# OptoSense.net
KiCad netlist of a schematic drawn in EAGLE
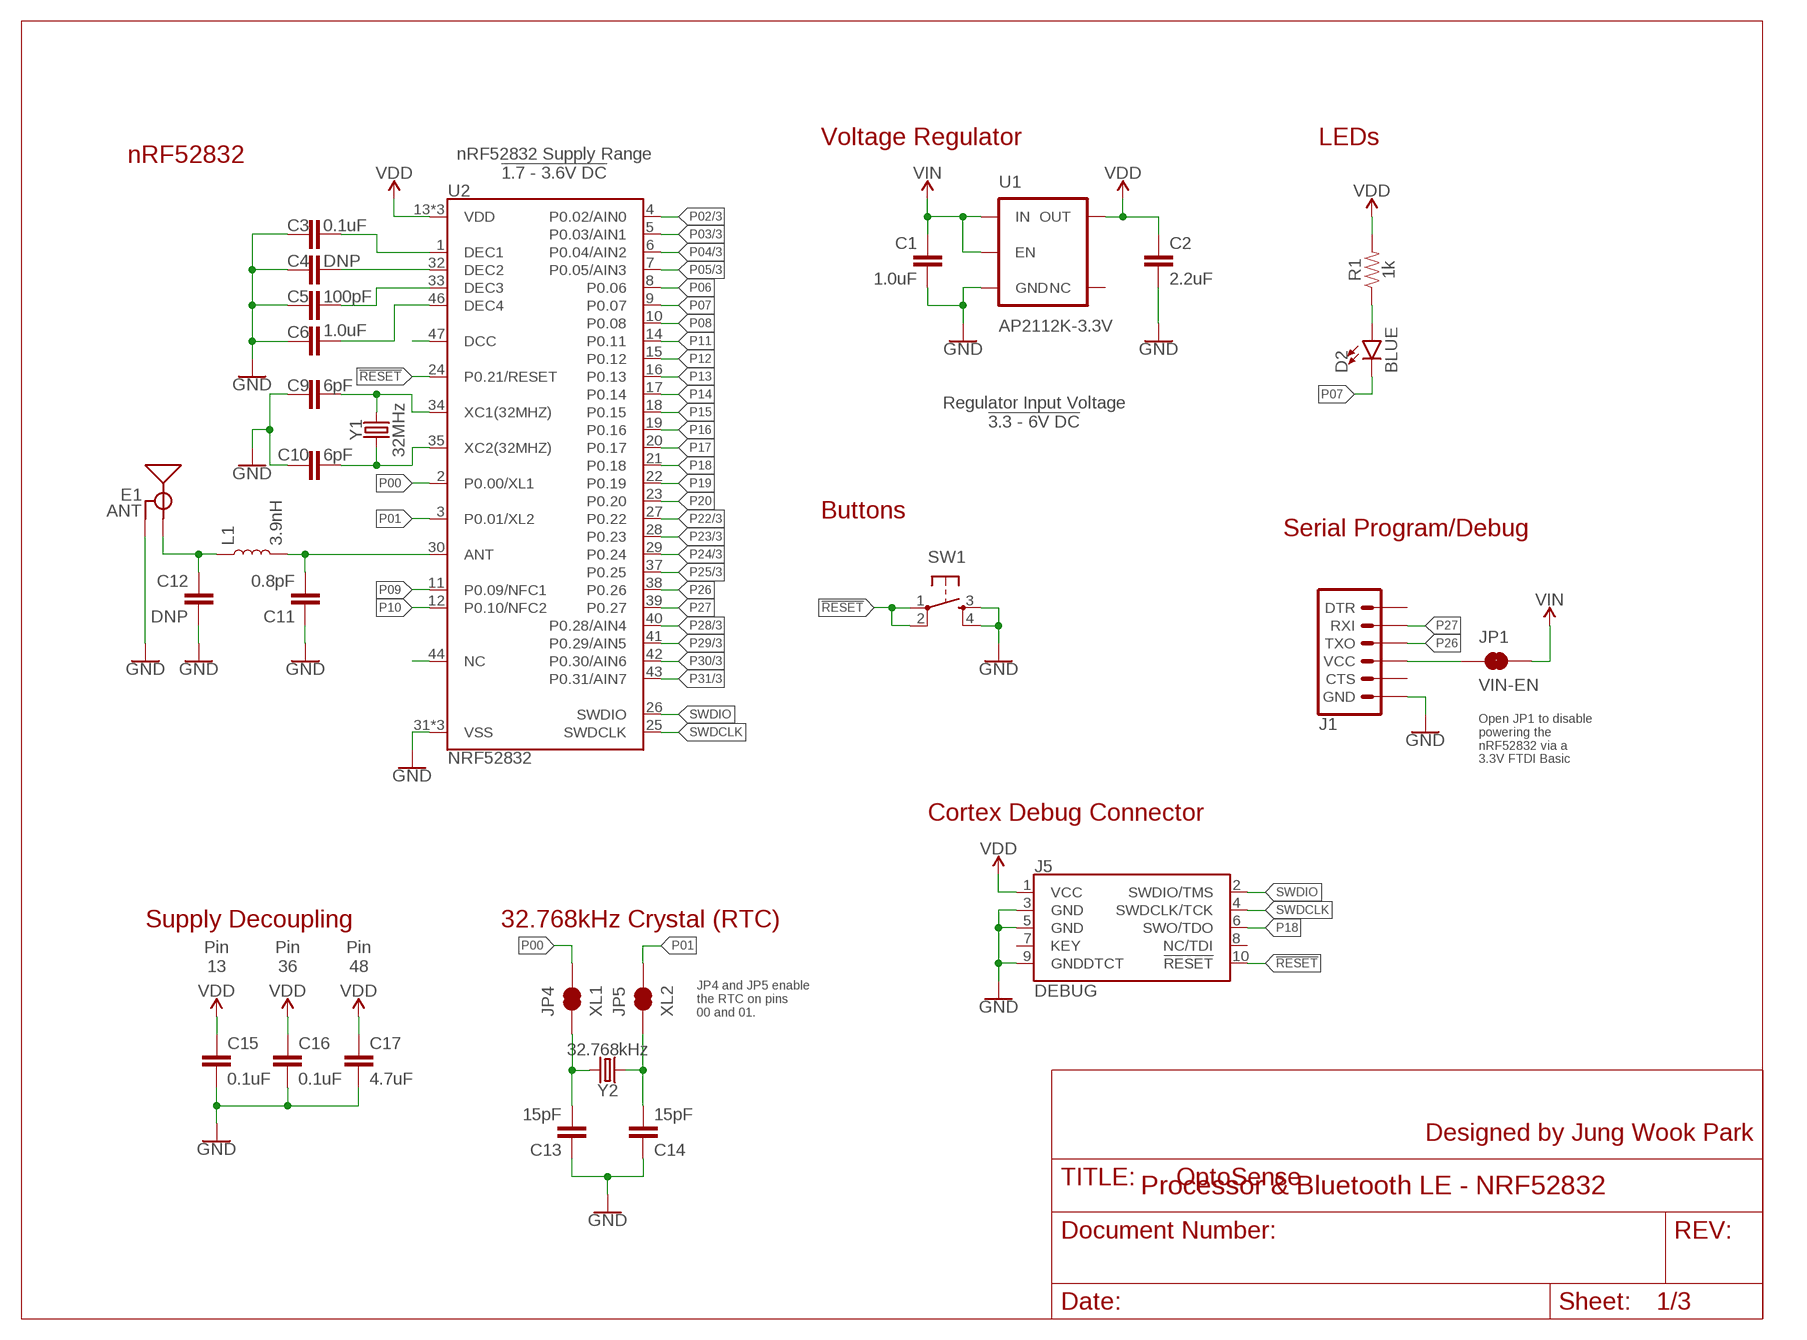
[diagram p0: schematic, sheet 1]
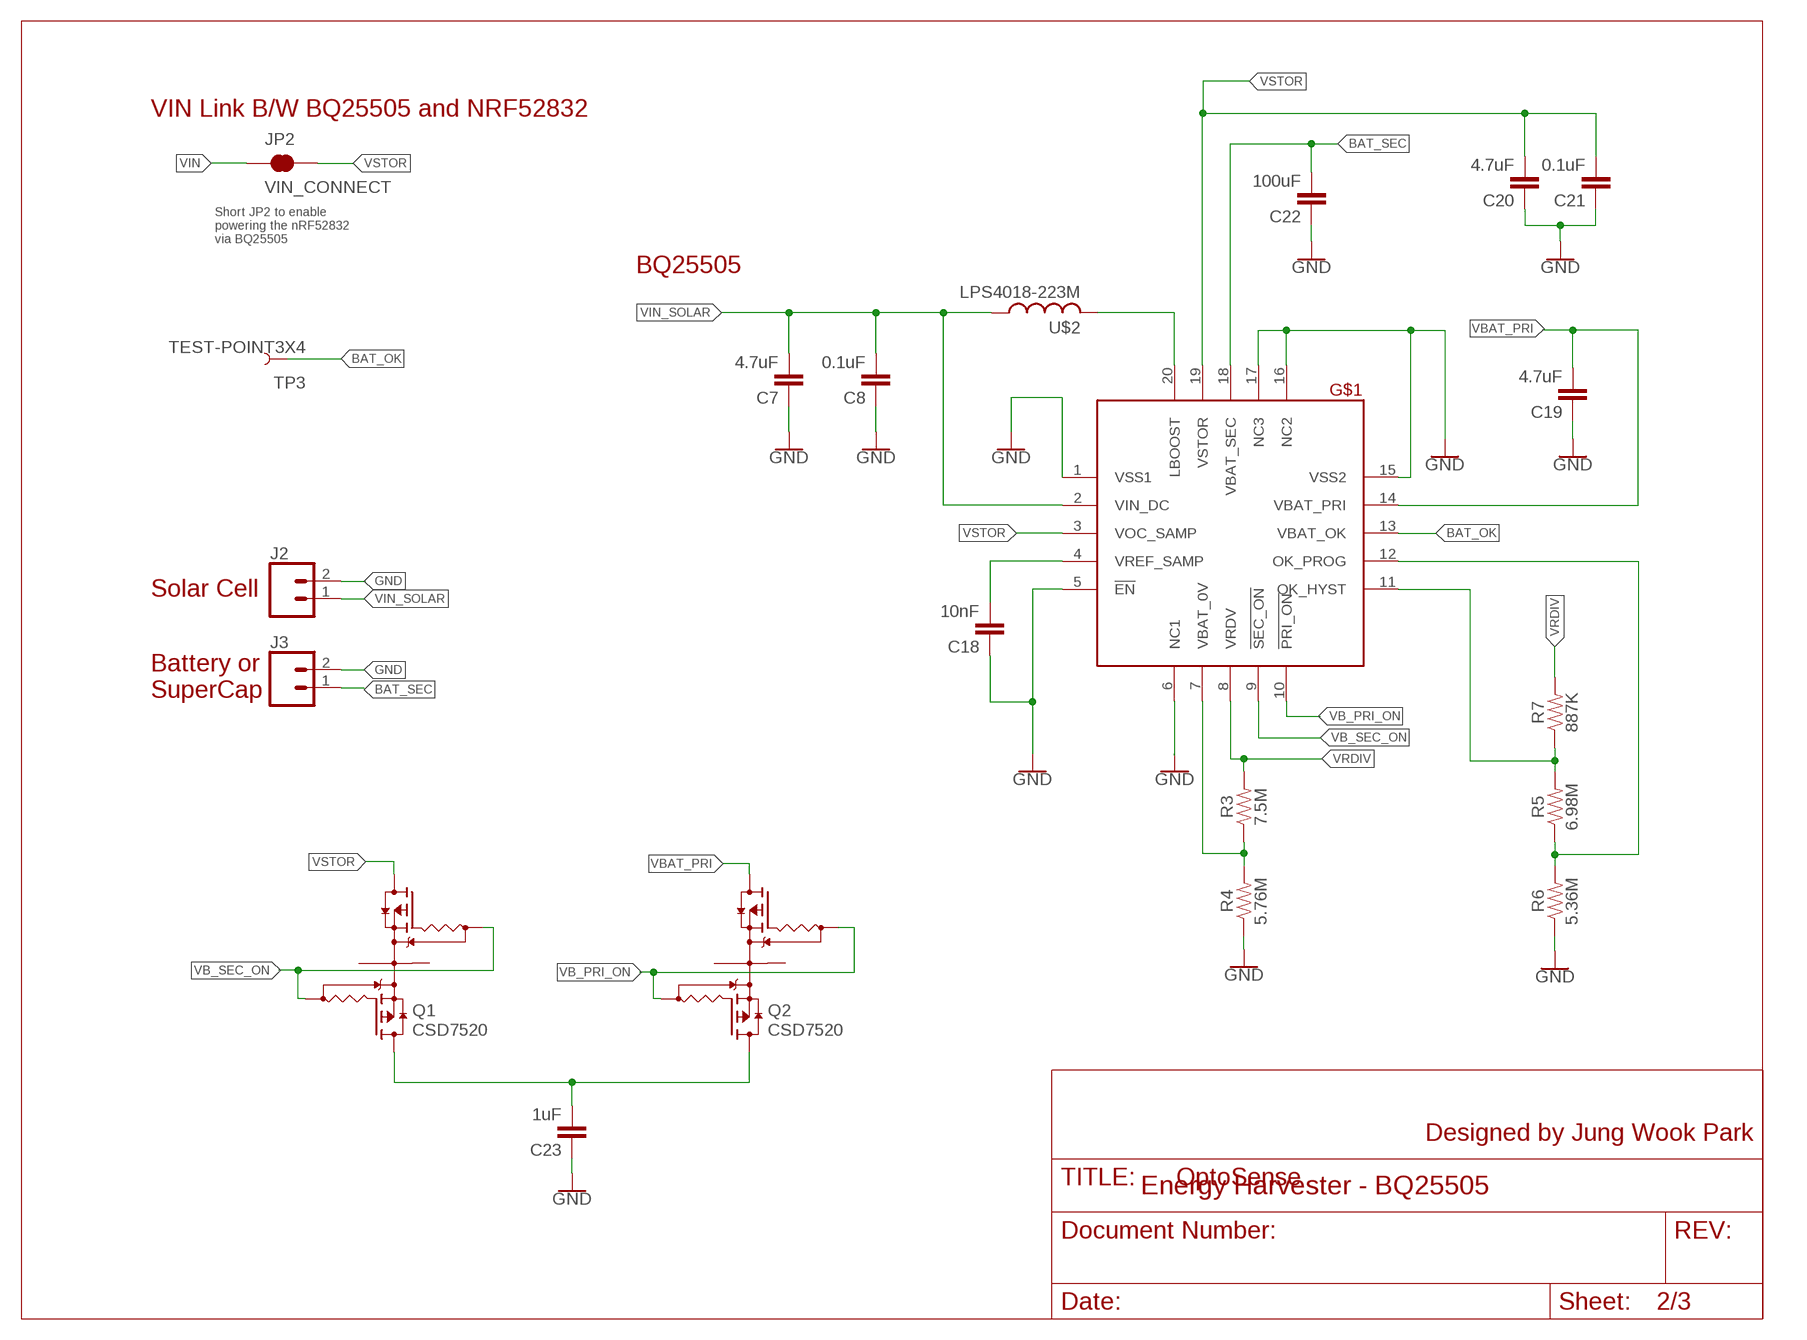
[diagram p1: schematic, sheet 2]
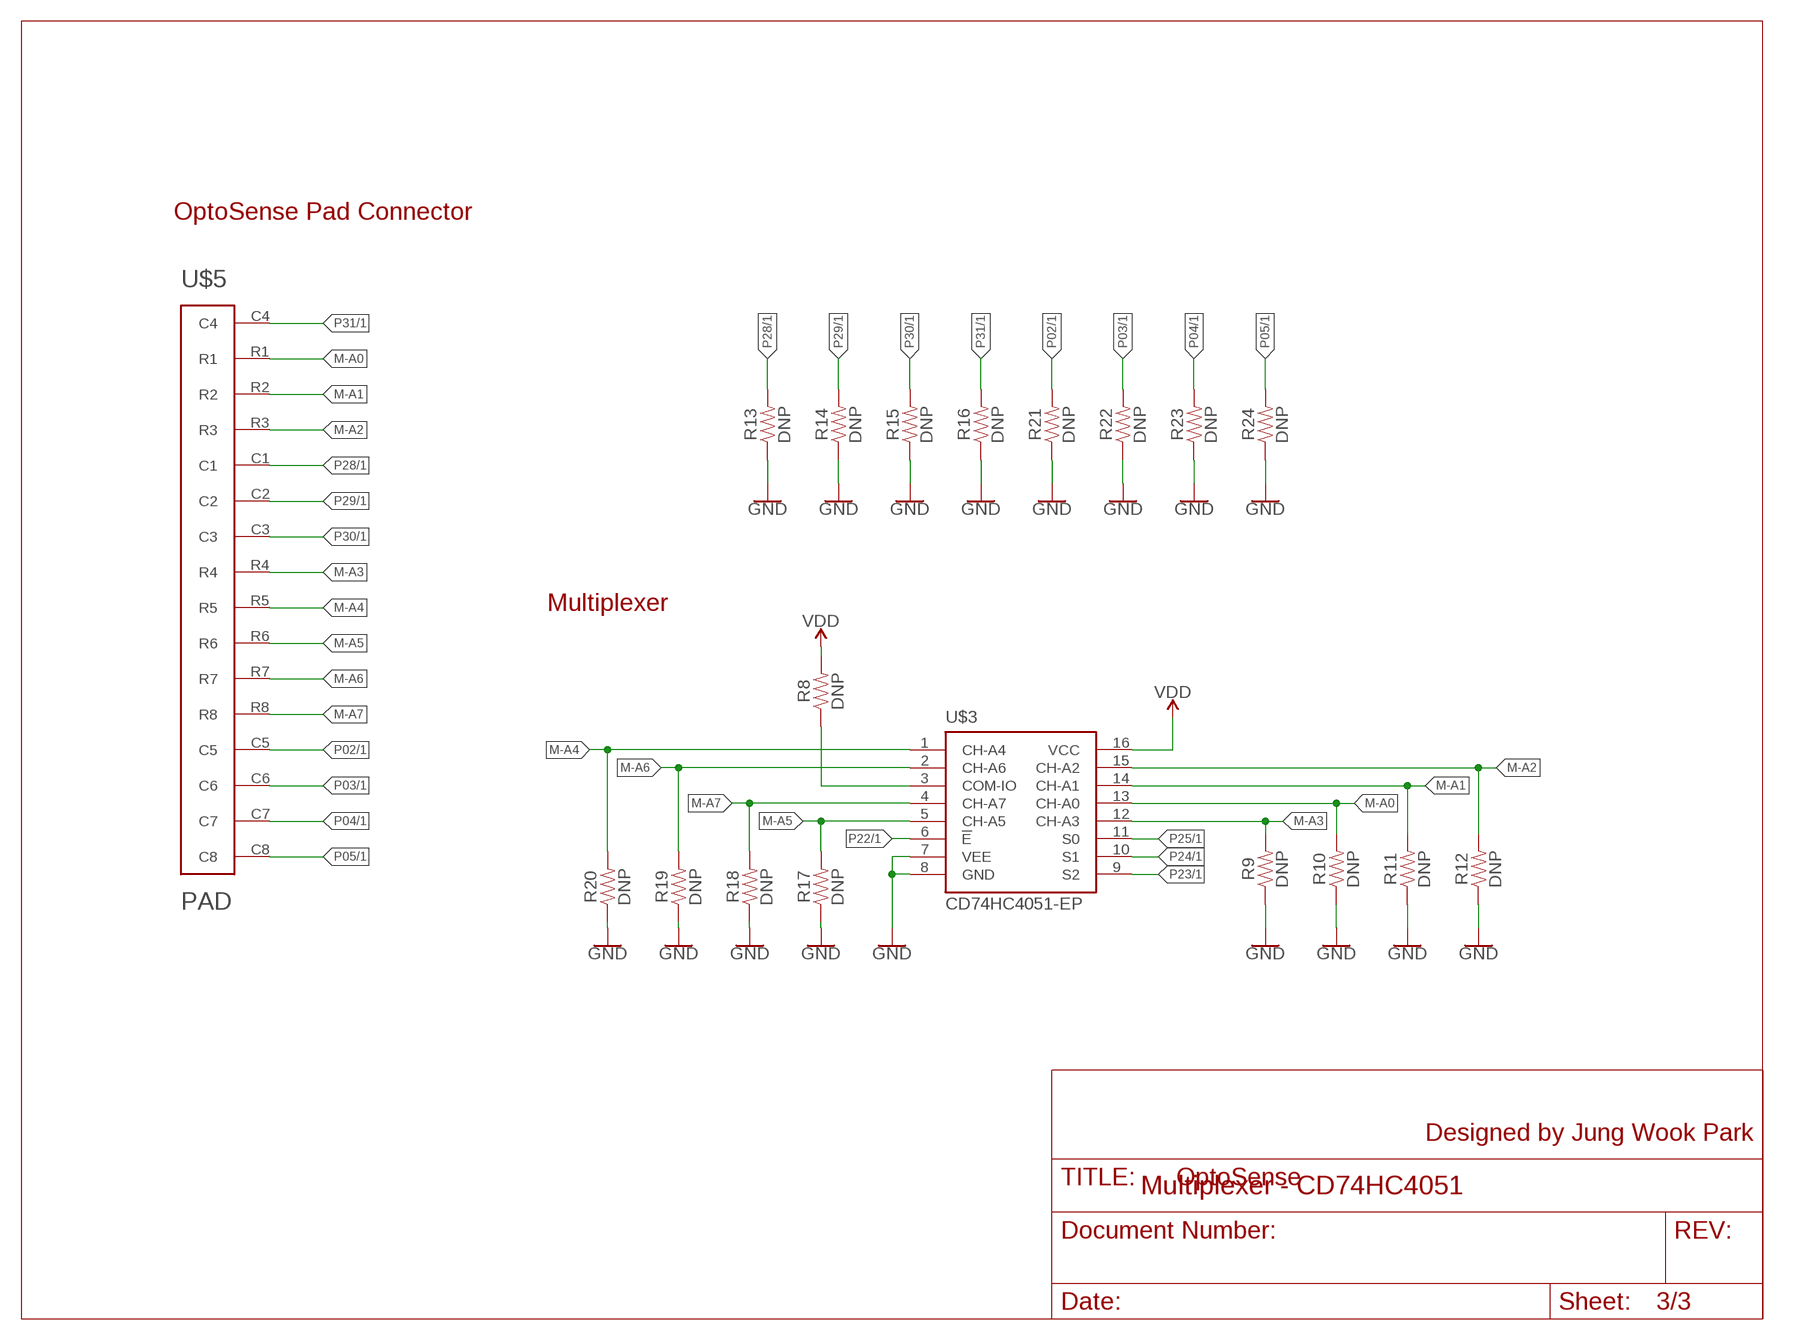
[diagram p2: schematic, sheet 3]

(export (version "E")
  (design (tool "Eeschema 10.0.6"))
  (components
    (comp (ref "C1")
      (value "1.0uF")
      (footprint "eagle-import:0603")
      (libsource (lib "eagle-import") (part "1.0UF-0603-16V-10%"))
    )
    (comp (ref "C2")
      (value "2.2uF")
      (footprint "eagle-import:0603")
      (libsource (lib "eagle-import") (part "2.2UF-0603-10V-20%"))
    )
    (comp (ref "C3")
      (value "0.1uF")
      (footprint "eagle-import:0402")
      (libsource (lib "eagle-import") (part "0.1UF-0402-16V-10%"))
    )
    (comp (ref "C4")
      (value "DNP")
      (footprint "eagle-import:0402")
      (libsource (lib "eagle-import") (part "CAP0402"))
    )
    (comp (ref "C5")
      (value "100pF")
      (footprint "eagle-import:0402")
      (libsource (lib "eagle-import") (part "100PF-0402-50V-5%"))
    )
    (comp (ref "C6")
      (value "1.0uF")
      (footprint "eagle-import:0402")
      (libsource (lib "eagle-import") (part "1.0UF-0402-16V-10%"))
    )
    (comp (ref "C9")
      (value "6pF")
      (footprint "eagle-import:0402")
      (libsource (lib "eagle-import") (part "6PF-0402-50V-0.5%"))
    )
    (comp (ref "C10")
      (value "6pF")
      (footprint "eagle-import:0402")
      (libsource (lib "eagle-import") (part "6PF-0402-50V-0.5%"))
    )
    (comp (ref "C11")
      (value "0.8pF")
      (footprint "eagle-import:0402")
      (libsource (lib "eagle-import") (part "0.8PF-0402-50V-0.1PF"))
    )
    (comp (ref "C12")
      (value "DNP")
      (footprint "eagle-import:0402")
      (libsource (lib "eagle-import") (part "CAP0402"))
    )
    (comp (ref "C13")
      (value "15pF")
      (footprint "eagle-import:0402")
      (libsource (lib "eagle-import") (part "15PF-0402-50V-5%"))
    )
    (comp (ref "C14")
      (value "15pF")
      (footprint "eagle-import:0402")
      (libsource (lib "eagle-import") (part "15PF-0402-50V-5%"))
    )
    (comp (ref "C15")
      (value "0.1uF")
      (footprint "eagle-import:0402")
      (libsource (lib "eagle-import") (part "0.1UF-0402-16V-10%"))
    )
    (comp (ref "C16")
      (value "0.1uF")
      (footprint "eagle-import:0402")
      (libsource (lib "eagle-import") (part "0.1UF-0402-16V-10%"))
    )
    (comp (ref "C17")
      (value "4.7uF")
      (footprint "eagle-import:0603")
      (libsource (lib "eagle-import") (part "4.7UF0603"))
    )
    (comp (ref "D2")
      (value "BLUE")
      (footprint "eagle-import:LED-0603")
      (libsource (lib "eagle-import") (part "LED-BLUE0603"))
    )
    (comp (ref "E1")
      (value "ANT")
      (footprint "eagle-import:TRACE_ANTENNA_2.4GHZ_15.2MM")
      (libsource (lib "eagle-import") (part "ANTENNA-GROUNDEDTRACE-15.2MM"))
    )
    (comp (ref "J1")
      (value "ARDUINO_SERIAL_PROGRAMPTH")
      (footprint "eagle-import:1X06")
      (libsource (lib "eagle-import") (part "ARDUINO_SERIAL_PROGRAMPTH"))
    )
    (comp (ref "J5")
      (value "DEBUG")
      (footprint "eagle-import:2X5-PTH-1.27MM")
      (libsource (lib "eagle-import") (part "CORTEX_DEBUGPTH"))
    )
    (comp (ref "JP1")
      (value "VIN-EN")
      (footprint "eagle-import:SMT-JUMPER_2_NC_TRACE_SILK")
      (libsource (lib "eagle-import") (part "JUMPER-SMT_2_NC_TRACE_SILK"))
    )
    (comp (ref "JP4")
      (value "XL1")
      (footprint "eagle-import:PAD-JUMPER-2-NC_BY_TRACE_YES_SILK")
      (libsource (lib "eagle-import") (part "JUMPER-PAD-2-NC_BY_TRACE"))
    )
    (comp (ref "JP5")
      (value "XL2")
      (footprint "eagle-import:PAD-JUMPER-2-NC_BY_TRACE_YES_SILK")
      (libsource (lib "eagle-import") (part "JUMPER-PAD-2-NC_BY_TRACE"))
    )
    (comp (ref "L1")
      (value "3.9nH")
      (footprint "eagle-import:0402")
      (libsource (lib "eagle-import") (part "INDUCTOR-0402-3.9NH"))
    )
    (comp (ref "R1")
      (value "1k")
      (footprint "eagle-import:0603")
      (libsource (lib "eagle-import") (part "1KOHM-0603-1/10W-1%"))
    )
    (comp (ref "SW1")
      (value "SWITCH_SPST_4_PINRECT")
      (footprint "eagle-import:TACTILE_SWITCH_SMD_4.6X2.8MM")
      (libsource (lib "eagle-import") (part "SWITCH_SPST_4_PINRECT"))
    )
    (comp (ref "U1")
      (value "AP2112K-3.3V")
      (footprint "eagle-import:SOT23-5")
      (libsource (lib "eagle-import") (part "V_REG_AP2112K-3.3V"))
    )
    (comp (ref "U2")
      (value "NRF52832")
      (footprint "eagle-import:QFN48-6X6MM")
      (libsource (lib "eagle-import") (part "NRF52832"))
    )
    (comp (ref "Y1")
      (value "32MHz")
      (footprint "eagle-import:CRYSTAL-SMD-2.0X1.6MM")
      (libsource (lib "eagle-import") (part "CRYSTAL-32MHZ-SMD-2.0X1.6MM"))
    )
    (comp (ref "Y2")
      (value "32.768kHz")
      (footprint "eagle-import:CRYSTAL-SMD-3.2X1.5MM")
      (libsource (lib "eagle-import") (part "CRYSTAL-32.768KHZSMD-3.2X1.5"))
    )
    (comp (ref "C7")
      (value "4.7uF")
      (footprint "eagle-import:0402")
      (libsource (lib "eagle-import") (part "0.8PF-0402-50V-0.1PF"))
    )
    (comp (ref "C8")
      (value "0.1uF")
      (footprint "eagle-import:0402")
      (libsource (lib "eagle-import") (part "0.8PF-0402-50V-0.1PF"))
    )
    (comp (ref "C18")
      (value "10nF")
      (footprint "eagle-import:0402")
      (libsource (lib "eagle-import") (part "0.8PF-0402-50V-0.1PF"))
    )
    (comp (ref "C19")
      (value "4.7uF")
      (footprint "eagle-import:0402")
      (libsource (lib "eagle-import") (part "0.8PF-0402-50V-0.1PF"))
    )
    (comp (ref "C20")
      (value "4.7uF")
      (footprint "eagle-import:0402")
      (libsource (lib "eagle-import") (part "0.8PF-0402-50V-0.1PF"))
    )
    (comp (ref "C21")
      (value "0.1uF")
      (footprint "eagle-import:0402")
      (libsource (lib "eagle-import") (part "0.8PF-0402-50V-0.1PF"))
    )
    (comp (ref "C22")
      (value "100uF")
      (footprint "eagle-import:0402")
      (libsource (lib "eagle-import") (part "0.8PF-0402-50V-0.1PF"))
    )
    (comp (ref "C23")
      (value "1uF")
      (footprint "eagle-import:0402")
      (libsource (lib "eagle-import") (part "0.8PF-0402-50V-0.1PF"))
    )
    (comp (ref "J2")
      (value "CONN_02")
      (footprint "eagle-import:1X02")
      (libsource (lib "eagle-import") (part "CONN_02"))
    )
    (comp (ref "J3")
      (value "CONN_02")
      (footprint "eagle-import:1X02")
      (libsource (lib "eagle-import") (part "CONN_02"))
    )
    (comp (ref "JP2")
      (value "VIN_CONNECT")
      (footprint "eagle-import:SMT-JUMPER_2_NC_TRACE_SILK")
      (libsource (lib "eagle-import") (part "JUMPER-SMT_2_NC_TRACE_SILK"))
    )
    (comp (ref "Q1")
      (value "CSD7520")
      (footprint "eagle-import:CSD75205W1015")
      (libsource (lib "eagle-import") (part "CSD75205W1015-BGA"))
    )
    (comp (ref "Q2")
      (value "CSD7520")
      (footprint "eagle-import:CSD75205W1015")
      (libsource (lib "eagle-import") (part "CSD75205W1015-BGA"))
    )
    (comp (ref "R3")
      (value "7.5M")
      (footprint "eagle-import:0603")
      (libsource (lib "eagle-import") (part "1KOHM-0603-1/10W-1%"))
    )
    (comp (ref "R4")
      (value "5.76M")
      (footprint "eagle-import:0603")
      (libsource (lib "eagle-import") (part "1KOHM-0603-1/10W-1%"))
    )
    (comp (ref "R5")
      (value "6.98M")
      (footprint "eagle-import:0603")
      (libsource (lib "eagle-import") (part "1KOHM-0603-1/10W-1%"))
    )
    (comp (ref "R6")
      (value "5.36M")
      (footprint "eagle-import:0603")
      (libsource (lib "eagle-import") (part "1KOHM-0603-1/10W-1%"))
    )
    (comp (ref "R7")
      (value "887K")
      (footprint "eagle-import:0603")
      (libsource (lib "eagle-import") (part "1KOHM-0603-1/10W-1%"))
    )
    (comp (ref "TP3")
      (value "TEST-POINT3X4")
      (footprint "eagle-import:PAD.03X.04")
      (libsource (lib "eagle-import") (part "TEST-POINT3X4"))
    )
    (comp (ref "U$1")
      (value "BQ25505")
      (footprint "eagle-import:QFN20")
      (libsource (lib "eagle-import") (part "BQ25505"))
    )
    (comp (ref "U$2")
      (value "LPS4018-223M")
      (footprint "eagle-import:LPS4018")
      (libsource (lib "eagle-import") (part "LPS4018"))
    )
    (comp (ref "R8")
      (value "DNP")
      (footprint "eagle-import:0603")
      (libsource (lib "eagle-import") (part "1KOHM-0603-1/10W-1%"))
    )
    (comp (ref "R9")
      (value "DNP")
      (footprint "eagle-import:0603")
      (libsource (lib "eagle-import") (part "1KOHM-0603-1/10W-1%"))
    )
    (comp (ref "R10")
      (value "DNP")
      (footprint "eagle-import:0603")
      (libsource (lib "eagle-import") (part "1KOHM-0603-1/10W-1%"))
    )
    (comp (ref "R11")
      (value "DNP")
      (footprint "eagle-import:0603")
      (libsource (lib "eagle-import") (part "1KOHM-0603-1/10W-1%"))
    )
    (comp (ref "R12")
      (value "DNP")
      (footprint "eagle-import:0603")
      (libsource (lib "eagle-import") (part "1KOHM-0603-1/10W-1%"))
    )
    (comp (ref "R13")
      (value "DNP")
      (footprint "eagle-import:0603")
      (libsource (lib "eagle-import") (part "1KOHM-0603-1/10W-1%"))
    )
    (comp (ref "R14")
      (value "DNP")
      (footprint "eagle-import:0603")
      (libsource (lib "eagle-import") (part "1KOHM-0603-1/10W-1%"))
    )
    (comp (ref "R15")
      (value "DNP")
      (footprint "eagle-import:0603")
      (libsource (lib "eagle-import") (part "1KOHM-0603-1/10W-1%"))
    )
    (comp (ref "R16")
      (value "DNP")
      (footprint "eagle-import:0603")
      (libsource (lib "eagle-import") (part "1KOHM-0603-1/10W-1%"))
    )
    (comp (ref "R17")
      (value "DNP")
      (footprint "eagle-import:0603")
      (libsource (lib "eagle-import") (part "1KOHM-0603-1/10W-1%"))
    )
    (comp (ref "R18")
      (value "DNP")
      (footprint "eagle-import:0603")
      (libsource (lib "eagle-import") (part "1KOHM-0603-1/10W-1%"))
    )
    (comp (ref "R19")
      (value "DNP")
      (footprint "eagle-import:0603")
      (libsource (lib "eagle-import") (part "1KOHM-0603-1/10W-1%"))
    )
    (comp (ref "R20")
      (value "DNP")
      (footprint "eagle-import:0603")
      (libsource (lib "eagle-import") (part "1KOHM-0603-1/10W-1%"))
    )
    (comp (ref "R21")
      (value "DNP")
      (footprint "eagle-import:0603")
      (libsource (lib "eagle-import") (part "1KOHM-0603-1/10W-1%"))
    )
    (comp (ref "R22")
      (value "DNP")
      (footprint "eagle-import:0603")
      (libsource (lib "eagle-import") (part "1KOHM-0603-1/10W-1%"))
    )
    (comp (ref "R23")
      (value "DNP")
      (footprint "eagle-import:0603")
      (libsource (lib "eagle-import") (part "1KOHM-0603-1/10W-1%"))
    )
    (comp (ref "R24")
      (value "DNP")
      (footprint "eagle-import:0603")
      (libsource (lib "eagle-import") (part "1KOHM-0603-1/10W-1%"))
    )
    (comp (ref "U$3")
      (value "CD74HC4051-EP")
      (footprint "eagle-import:SO16")
      (libsource (lib "eagle-import") (part "CD74HC4051-EP"))
    )
    (comp (ref "U$5")
      (value "PAD")
      (footprint "eagle-import:PADS-16")
      (libsource (lib "eagle-import") (part "OPTOSENSE_PAD_CONNECTOR16"))
    )
  )
  (nets
    (net (code "1") (name "BAT_OK") (class "Default")
      (node (ref "TP3") (pin "P$1") (pinfunction "1_P$1") (pintype "bidirectional"))
      (node (ref "U$1") (pin "13") (pinfunction "VBAT_OK_13") (pintype "bidirectional"))
    )
    (net (code "2") (name "BAT_SEC") (class "Default")
      (node (ref "C22") (pin "2") (pinfunction "2_2") (pintype "passive"))
      (node (ref "J3") (pin "1") (pinfunction "1_1") (pintype "passive"))
      (node (ref "U$1") (pin "18") (pinfunction "VBAT_SEC_18") (pintype "bidirectional"))
    )
    (net (code "3") (name "GND") (class "Default")
      (node (ref "C1") (pin "2") (pinfunction "2_2") (pintype "passive"))
      (node (ref "C10") (pin "2") (pinfunction "2_2") (pintype "passive"))
      (node (ref "C11") (pin "1") (pinfunction "1_1") (pintype "passive"))
      (node (ref "C12") (pin "2") (pinfunction "2_2") (pintype "passive"))
      (node (ref "C13") (pin "1") (pinfunction "1_1") (pintype "passive"))
      (node (ref "C14") (pin "1") (pinfunction "1_1") (pintype "passive"))
      (node (ref "C15") (pin "2") (pinfunction "2_2") (pintype "passive"))
      (node (ref "C16") (pin "2") (pinfunction "2_2") (pintype "passive"))
      (node (ref "C17") (pin "2") (pinfunction "2_2") (pintype "passive"))
      (node (ref "C18") (pin "1") (pinfunction "1_1") (pintype "passive"))
      (node (ref "C19") (pin "1") (pinfunction "1_1") (pintype "passive"))
      (node (ref "C2") (pin "2") (pinfunction "2_2") (pintype "passive"))
      (node (ref "C20") (pin "1") (pinfunction "1_1") (pintype "passive"))
      (node (ref "C21") (pin "1") (pinfunction "1_1") (pintype "passive"))
      (node (ref "C22") (pin "1") (pinfunction "1_1") (pintype "passive"))
      (node (ref "C23") (pin "1") (pinfunction "1_1") (pintype "passive"))
      (node (ref "C3") (pin "1") (pinfunction "1_1") (pintype "passive"))
      (node (ref "C4") (pin "1") (pinfunction "1_1") (pintype "passive"))
      (node (ref "C5") (pin "1") (pinfunction "1_1") (pintype "passive"))
      (node (ref "C6") (pin "1") (pinfunction "1_1") (pintype "passive"))
      (node (ref "C7") (pin "1") (pinfunction "1_1") (pintype "passive"))
      (node (ref "C8") (pin "1") (pinfunction "1_1") (pintype "passive"))
      (node (ref "C9") (pin "1") (pinfunction "1_1") (pintype "passive"))
      (node (ref "E1") (pin "GND") (pinfunction "GND_GND") (pintype "bidirectional"))
      (node (ref "J1") (pin "6") (pinfunction "GND_6") (pintype "passive"))
      (node (ref "J2") (pin "2") (pinfunction "2_2") (pintype "passive"))
      (node (ref "J3") (pin "2") (pinfunction "2_2") (pintype "passive"))
      (node (ref "J5") (pin "3") (pinfunction "GND_3") (pintype "bidirectional"))
      (node (ref "J5") (pin "5") (pinfunction "GND_5") (pintype "bidirectional"))
      (node (ref "J5") (pin "9") (pinfunction "GNDDTCT_9") (pintype "bidirectional"))
      (node (ref "R10") (pin "1") (pinfunction "1_1") (pintype "passive"))
      (node (ref "R11") (pin "1") (pinfunction "1_1") (pintype "passive"))
      (node (ref "R12") (pin "1") (pinfunction "1_1") (pintype "passive"))
      (node (ref "R13") (pin "1") (pinfunction "1_1") (pintype "passive"))
      (node (ref "R14") (pin "1") (pinfunction "1_1") (pintype "passive"))
      (node (ref "R15") (pin "1") (pinfunction "1_1") (pintype "passive"))
      (node (ref "R16") (pin "1") (pinfunction "1_1") (pintype "passive"))
      (node (ref "R17") (pin "1") (pinfunction "1_1") (pintype "passive"))
      (node (ref "R18") (pin "1") (pinfunction "1_1") (pintype "passive"))
      (node (ref "R19") (pin "1") (pinfunction "1_1") (pintype "passive"))
      (node (ref "R20") (pin "1") (pinfunction "1_1") (pintype "passive"))
      (node (ref "R21") (pin "1") (pinfunction "1_1") (pintype "passive"))
      (node (ref "R22") (pin "1") (pinfunction "1_1") (pintype "passive"))
      (node (ref "R23") (pin "1") (pinfunction "1_1") (pintype "passive"))
      (node (ref "R24") (pin "1") (pinfunction "1_1") (pintype "passive"))
      (node (ref "R4") (pin "1") (pinfunction "1_1") (pintype "passive"))
      (node (ref "R6") (pin "1") (pinfunction "1_1") (pintype "passive"))
      (node (ref "R9") (pin "1") (pinfunction "1_1") (pintype "passive"))
      (node (ref "SW1") (pin "3") (pinfunction "3_3") (pintype "passive"))
      (node (ref "SW1") (pin "4") (pinfunction "4_4") (pintype "passive"))
      (node (ref "U$1") (pin "1") (pinfunction "VSS1_1") (pintype "bidirectional"))
      (node (ref "U$1") (pin "15") (pinfunction "VSS2_15") (pintype "bidirectional"))
      (node (ref "U$1") (pin "16") (pinfunction "NC2_16") (pintype "bidirectional"))
      (node (ref "U$1") (pin "17") (pinfunction "NC3_17") (pintype "bidirectional"))
      (node (ref "U$1") (pin "5") (pinfunction "~{EN}_5") (pintype "bidirectional"))
      (node (ref "U$1") (pin "6") (pinfunction "NC1_6") (pintype "bidirectional"))
      (node (ref "U$3") (pin "7") (pinfunction "VEE_7") (pintype "bidirectional"))
      (node (ref "U$3") (pin "8") (pinfunction "GND_8") (pintype "bidirectional"))
      (node (ref "U1") (pin "2") (pinfunction "GND_2") (pintype "input"))
      (node (ref "U2") (pin "31") (pinfunction "VSS_31") (pintype "bidirectional"))
      (node (ref "U2") (pin "45") (pinfunction "VSS_45") (pintype "bidirectional"))
      (node (ref "U2") (pin "EP") (pinfunction "VSS_EP") (pintype "bidirectional"))
    )
    (net (code "4") (name "M-A0") (class "Default")
      (node (ref "R10") (pin "2") (pinfunction "2_2") (pintype "passive"))
      (node (ref "U$3") (pin "13") (pinfunction "CH-A0_13") (pintype "bidirectional"))
      (node (ref "U$5") (pin "R1") (pinfunction "R1_R1") (pintype "bidirectional"))
    )
    (net (code "5") (name "M-A1") (class "Default")
      (node (ref "R11") (pin "2") (pinfunction "2_2") (pintype "passive"))
      (node (ref "U$3") (pin "14") (pinfunction "CH-A1_14") (pintype "bidirectional"))
      (node (ref "U$5") (pin "R2") (pinfunction "R2_R2") (pintype "bidirectional"))
    )
    (net (code "6") (name "M-A2") (class "Default")
      (node (ref "R12") (pin "2") (pinfunction "2_2") (pintype "passive"))
      (node (ref "U$3") (pin "15") (pinfunction "CH-A2_15") (pintype "bidirectional"))
      (node (ref "U$5") (pin "R3") (pinfunction "R3_R3") (pintype "bidirectional"))
    )
    (net (code "7") (name "M-A3") (class "Default")
      (node (ref "R9") (pin "2") (pinfunction "2_2") (pintype "passive"))
      (node (ref "U$3") (pin "12") (pinfunction "CH-A3_12") (pintype "bidirectional"))
      (node (ref "U$5") (pin "R4") (pinfunction "R4_R4") (pintype "bidirectional"))
    )
    (net (code "8") (name "M-A4") (class "Default")
      (node (ref "R20") (pin "2") (pinfunction "2_2") (pintype "passive"))
      (node (ref "U$3") (pin "1") (pinfunction "CH-A4_1") (pintype "bidirectional"))
      (node (ref "U$5") (pin "R5") (pinfunction "R5_R5") (pintype "bidirectional"))
    )
    (net (code "9") (name "M-A5") (class "Default")
      (node (ref "R17") (pin "2") (pinfunction "2_2") (pintype "passive"))
      (node (ref "U$3") (pin "5") (pinfunction "CH-A5_5") (pintype "bidirectional"))
      (node (ref "U$5") (pin "R6") (pinfunction "R6_R6") (pintype "bidirectional"))
    )
    (net (code "10") (name "M-A6") (class "Default")
      (node (ref "R19") (pin "2") (pinfunction "2_2") (pintype "passive"))
      (node (ref "U$3") (pin "2") (pinfunction "CH-A6_2") (pintype "bidirectional"))
      (node (ref "U$5") (pin "R7") (pinfunction "R7_R7") (pintype "bidirectional"))
    )
    (net (code "11") (name "M-A7") (class "Default")
      (node (ref "R18") (pin "2") (pinfunction "2_2") (pintype "passive"))
      (node (ref "U$3") (pin "4") (pinfunction "CH-A7_4") (pintype "bidirectional"))
      (node (ref "U$5") (pin "R8") (pinfunction "R8_R8") (pintype "bidirectional"))
    )
    (net (code "12") (name "Net-(C23-Pad2)") (class "Default")
      (node (ref "C23") (pin "2") (pinfunction "2_2") (pintype "passive"))
      (node (ref "Q1") (pin "D1") (pinfunction "D1_D1") (pintype "passive"))
      (node (ref "Q2") (pin "D1") (pinfunction "D1_D1") (pintype "passive"))
    )
    (net (code "13") (name "Net-(D2-PadA)") (class "Default")
      (node (ref "D2") (pin "A") (pinfunction "A_A") (pintype "passive"))
      (node (ref "R1") (pin "1") (pinfunction "1_1") (pintype "passive"))
    )
    (net (code "14") (name "Net-(E1-SIGNAL)") (class "Default")
      (node (ref "C12") (pin "1") (pinfunction "1_1") (pintype "passive"))
      (node (ref "E1") (pin "ANT") (pinfunction "SIGNAL_ANT") (pintype "bidirectional"))
      (node (ref "L1") (pin "1") (pinfunction "1_1") (pintype "passive"))
    )
    (net (code "15") (name "Net-(J1-VCC)") (class "Default")
      (node (ref "J1") (pin "4") (pinfunction "VCC_4") (pintype "passive"))
      (node (ref "JP1") (pin "1") (pinfunction "1_1") (pintype "passive"))
    )
    (net (code "16") (name "Net-(U$1-LBOOST)") (class "Default")
      (node (ref "U$1") (pin "20") (pinfunction "LBOOST_20") (pintype "bidirectional"))
      (node (ref "U$2") (pin "P$2") (pinfunction "2_P$2") (pintype "passive"))
    )
    (net (code "17") (name "Net-(U$1-OK_HYST)") (class "Default")
      (node (ref "R5") (pin "2") (pinfunction "2_2") (pintype "passive"))
      (node (ref "R7") (pin "1") (pinfunction "1_1") (pintype "passive"))
      (node (ref "U$1") (pin "11") (pinfunction "OK_HYST_11") (pintype "bidirectional"))
    )
    (net (code "18") (name "Net-(U$1-OK_PROG)") (class "Default")
      (node (ref "R5") (pin "1") (pinfunction "1_1") (pintype "passive"))
      (node (ref "R6") (pin "2") (pinfunction "2_2") (pintype "passive"))
      (node (ref "U$1") (pin "12") (pinfunction "OK_PROG_12") (pintype "bidirectional"))
    )
    (net (code "19") (name "Net-(U$1-VBAT_0V)") (class "Default")
      (node (ref "R3") (pin "1") (pinfunction "1_1") (pintype "passive"))
      (node (ref "R4") (pin "2") (pinfunction "2_2") (pintype "passive"))
      (node (ref "U$1") (pin "7") (pinfunction "VBAT_0V_7") (pintype "bidirectional"))
    )
    (net (code "20") (name "Net-(U$1-VREF_SAMP)") (class "Default")
      (node (ref "C18") (pin "2") (pinfunction "2_2") (pintype "passive"))
      (node (ref "U$1") (pin "4") (pinfunction "VREF_SAMP_4") (pintype "bidirectional"))
    )
    (net (code "21") (name "Net-(U$3-COM-IO)") (class "Default")
      (node (ref "R8") (pin "1") (pinfunction "1_1") (pintype "passive"))
      (node (ref "U$3") (pin "3") (pinfunction "COM-IO_3") (pintype "bidirectional"))
    )
    (net (code "22") (name "Net-(U2-ANT)") (class "Default")
      (node (ref "C11") (pin "2") (pinfunction "2_2") (pintype "passive"))
      (node (ref "L1") (pin "2") (pinfunction "2_2") (pintype "passive"))
      (node (ref "U2") (pin "30") (pinfunction "ANT_30") (pintype "bidirectional"))
    )
    (net (code "23") (name "Net-(U2-DEC1)") (class "Default")
      (node (ref "C3") (pin "2") (pinfunction "2_2") (pintype "passive"))
      (node (ref "U2") (pin "1") (pinfunction "DEC1_1") (pintype "bidirectional"))
    )
    (net (code "24") (name "Net-(U2-DEC2)") (class "Default")
      (node (ref "C4") (pin "2") (pinfunction "2_2") (pintype "passive"))
      (node (ref "U2") (pin "32") (pinfunction "DEC2_32") (pintype "bidirectional"))
    )
    (net (code "25") (name "Net-(U2-DEC3)") (class "Default")
      (node (ref "C5") (pin "2") (pinfunction "2_2") (pintype "passive"))
      (node (ref "U2") (pin "33") (pinfunction "DEC3_33") (pintype "bidirectional"))
    )
    (net (code "26") (name "Net-(U2-DEC4)") (class "Default")
      (node (ref "C6") (pin "2") (pinfunction "2_2") (pintype "passive"))
      (node (ref "U2") (pin "46") (pinfunction "DEC4_46") (pintype "bidirectional"))
    )
    (net (code "27") (name "Net-(U2-XC1(32MHZ))") (class "Default")
      (node (ref "C9") (pin "2") (pinfunction "2_2") (pintype "passive"))
      (node (ref "U2") (pin "34") (pinfunction "XC1(32MHZ)_34") (pintype "bidirectional"))
      (node (ref "Y1") (pin "3") (pinfunction "2_3") (pintype "passive"))
    )
    (net (code "28") (name "Net-(U2-XC2(32MHZ))") (class "Default")
      (node (ref "C10") (pin "1") (pinfunction "1_1") (pintype "passive"))
      (node (ref "U2") (pin "35") (pinfunction "XC2(32MHZ)_35") (pintype "bidirectional"))
      (node (ref "Y1") (pin "1") (pinfunction "1_1") (pintype "passive"))
    )
    (net (code "29") (name "Net-(Y2-1)") (class "Default")
      (node (ref "C14") (pin "2") (pinfunction "2_2") (pintype "passive"))
      (node (ref "JP5") (pin "1") (pinfunction "1_1") (pintype "passive"))
      (node (ref "Y2") (pin "P$1") (pinfunction "1_P$1") (pintype "passive"))
    )
    (net (code "30") (name "Net-(Y2-2)") (class "Default")
      (node (ref "C13") (pin "2") (pinfunction "2_2") (pintype "passive"))
      (node (ref "JP4") (pin "1") (pinfunction "1_1") (pintype "passive"))
      (node (ref "Y2") (pin "P$2") (pinfunction "2_P$2") (pintype "passive"))
    )
    (net (code "31") (name "P00") (class "Default")
      (node (ref "JP4") (pin "2") (pinfunction "2_2") (pintype "passive"))
      (node (ref "U2") (pin "2") (pinfunction "P0.00/XL1_2") (pintype "bidirectional"))
    )
    (net (code "32") (name "P01") (class "Default")
      (node (ref "JP5") (pin "2") (pinfunction "2_2") (pintype "passive"))
      (node (ref "U2") (pin "3") (pinfunction "P0.01/XL2_3") (pintype "bidirectional"))
    )
    (net (code "33") (name "P02") (class "Default")
      (node (ref "R21") (pin "2") (pinfunction "2_2") (pintype "passive"))
      (node (ref "U$5") (pin "C5") (pinfunction "C5_C5") (pintype "bidirectional"))
      (node (ref "U2") (pin "4") (pinfunction "P0.02/AIN0_4") (pintype "bidirectional"))
    )
    (net (code "34") (name "P03") (class "Default")
      (node (ref "R22") (pin "2") (pinfunction "2_2") (pintype "passive"))
      (node (ref "U$5") (pin "C6") (pinfunction "C6_C6") (pintype "bidirectional"))
      (node (ref "U2") (pin "5") (pinfunction "P0.03/AIN1_5") (pintype "bidirectional"))
    )
    (net (code "35") (name "P04") (class "Default")
      (node (ref "R23") (pin "2") (pinfunction "2_2") (pintype "passive"))
      (node (ref "U$5") (pin "C7") (pinfunction "C7_C7") (pintype "bidirectional"))
      (node (ref "U2") (pin "6") (pinfunction "P0.04/AIN2_6") (pintype "bidirectional"))
    )
    (net (code "36") (name "P05") (class "Default")
      (node (ref "R24") (pin "2") (pinfunction "2_2") (pintype "passive"))
      (node (ref "U$5") (pin "C8") (pinfunction "C8_C8") (pintype "bidirectional"))
      (node (ref "U2") (pin "7") (pinfunction "P0.05/AIN3_7") (pintype "bidirectional"))
    )
    (net (code "37") (name "P06") (class "Default")
      (node (ref "U2") (pin "8") (pinfunction "P0.06_8") (pintype "bidirectional"))
    )
    (net (code "38") (name "P07") (class "Default")
      (node (ref "D2") (pin "C") (pinfunction "C_C") (pintype "passive"))
      (node (ref "U2") (pin "9") (pinfunction "P0.07_9") (pintype "bidirectional"))
    )
    (net (code "39") (name "P08") (class "Default")
      (node (ref "U2") (pin "10") (pinfunction "P0.08_10") (pintype "bidirectional"))
    )
    (net (code "40") (name "P09") (class "Default")
      (node (ref "U2") (pin "11") (pinfunction "P0.09/NFC1_11") (pintype "bidirectional"))
    )
    (net (code "41") (name "P10") (class "Default")
      (node (ref "U2") (pin "12") (pinfunction "P0.10/NFC2_12") (pintype "bidirectional"))
    )
    (net (code "42") (name "P11") (class "Default")
      (node (ref "U2") (pin "14") (pinfunction "P0.11_14") (pintype "bidirectional"))
    )
    (net (code "43") (name "P12") (class "Default")
      (node (ref "U2") (pin "15") (pinfunction "P0.12_15") (pintype "bidirectional"))
    )
    (net (code "44") (name "P13") (class "Default")
      (node (ref "U2") (pin "16") (pinfunction "P0.13_16") (pintype "bidirectional"))
    )
    (net (code "45") (name "P14") (class "Default")
      (node (ref "U2") (pin "17") (pinfunction "P0.14_17") (pintype "bidirectional"))
    )
    (net (code "46") (name "P15") (class "Default")
      (node (ref "U2") (pin "18") (pinfunction "P0.15_18") (pintype "bidirectional"))
    )
    (net (code "47") (name "P16") (class "Default")
      (node (ref "U2") (pin "19") (pinfunction "P0.16_19") (pintype "bidirectional"))
    )
    (net (code "48") (name "P17") (class "Default")
      (node (ref "U2") (pin "20") (pinfunction "P0.17_20") (pintype "bidirectional"))
    )
    (net (code "49") (name "P18") (class "Default")
      (node (ref "J5") (pin "6") (pinfunction "SWO/TDO_6") (pintype "bidirectional"))
      (node (ref "U2") (pin "21") (pinfunction "P0.18_21") (pintype "bidirectional"))
    )
    (net (code "50") (name "P19") (class "Default")
      (node (ref "U2") (pin "22") (pinfunction "P0.19_22") (pintype "bidirectional"))
    )
    (net (code "51") (name "P20") (class "Default")
      (node (ref "U2") (pin "23") (pinfunction "P0.20_23") (pintype "bidirectional"))
    )
    (net (code "52") (name "P22") (class "Default")
      (node (ref "U$3") (pin "6") (pinfunction "~{E}_6") (pintype "bidirectional"))
      (node (ref "U2") (pin "27") (pinfunction "P0.22_27") (pintype "bidirectional"))
    )
    (net (code "53") (name "P23") (class "Default")
      (node (ref "U$3") (pin "9") (pinfunction "S2_9") (pintype "bidirectional"))
      (node (ref "U2") (pin "28") (pinfunction "P0.23_28") (pintype "bidirectional"))
    )
    (net (code "54") (name "P24") (class "Default")
      (node (ref "U$3") (pin "10") (pinfunction "S1_10") (pintype "bidirectional"))
      (node (ref "U2") (pin "29") (pinfunction "P0.24_29") (pintype "bidirectional"))
    )
    (net (code "55") (name "P25") (class "Default")
      (node (ref "U$3") (pin "11") (pinfunction "S0_11") (pintype "bidirectional"))
      (node (ref "U2") (pin "37") (pinfunction "P0.25_37") (pintype "bidirectional"))
    )
    (net (code "56") (name "P26") (class "Default")
      (node (ref "J1") (pin "3") (pinfunction "TXO_3") (pintype "passive"))
      (node (ref "U2") (pin "38") (pinfunction "P0.26_38") (pintype "bidirectional"))
    )
    (net (code "57") (name "P27") (class "Default")
      (node (ref "J1") (pin "2") (pinfunction "RXI_2") (pintype "passive"))
      (node (ref "U2") (pin "39") (pinfunction "P0.27_39") (pintype "bidirectional"))
    )
    (net (code "58") (name "P28") (class "Default")
      (node (ref "R13") (pin "2") (pinfunction "2_2") (pintype "passive"))
      (node (ref "U$5") (pin "C1") (pinfunction "C1_C1") (pintype "bidirectional"))
      (node (ref "U2") (pin "40") (pinfunction "P0.28/AIN4_40") (pintype "bidirectional"))
    )
    (net (code "59") (name "P29") (class "Default")
      (node (ref "R14") (pin "2") (pinfunction "2_2") (pintype "passive"))
      (node (ref "U$5") (pin "C2") (pinfunction "C2_C2") (pintype "bidirectional"))
      (node (ref "U2") (pin "41") (pinfunction "P0.29/AIN5_41") (pintype "bidirectional"))
    )
    (net (code "60") (name "P30") (class "Default")
      (node (ref "R15") (pin "2") (pinfunction "2_2") (pintype "passive"))
      (node (ref "U$5") (pin "C3") (pinfunction "C3_C3") (pintype "bidirectional"))
      (node (ref "U2") (pin "42") (pinfunction "P0.30/AIN6_42") (pintype "bidirectional"))
    )
    (net (code "61") (name "P31") (class "Default")
      (node (ref "R16") (pin "2") (pinfunction "2_2") (pintype "passive"))
      (node (ref "U$5") (pin "C4") (pinfunction "C4_C4") (pintype "bidirectional"))
      (node (ref "U2") (pin "43") (pinfunction "P0.31/AIN7_43") (pintype "bidirectional"))
    )
    (net (code "62") (name "SWDCLK") (class "Default")
      (node (ref "J5") (pin "4") (pinfunction "SWDCLK/TCK_4") (pintype "bidirectional"))
      (node (ref "U2") (pin "25") (pinfunction "SWDCLK_25") (pintype "bidirectional"))
    )
    (net (code "63") (name "SWDIO") (class "Default")
      (node (ref "J5") (pin "2") (pinfunction "SWDIO/TMS_2") (pintype "bidirectional"))
      (node (ref "U2") (pin "26") (pinfunction "SWDIO_26") (pintype "bidirectional"))
    )
    (net (code "64") (name "VBAT_PRI") (class "Default")
      (node (ref "C19") (pin "2") (pinfunction "2_2") (pintype "passive"))
      (node (ref "Q2") (pin "D2") (pinfunction "D2_D2") (pintype "passive"))
      (node (ref "U$1") (pin "14") (pinfunction "VBAT_PRI_14") (pintype "bidirectional"))
    )
    (net (code "65") (name "VB_PRI_ON") (class "Default")
      (node (ref "Q2") (pin "G1") (pinfunction "G1_G1") (pintype "passive"))
      (node (ref "Q2") (pin "G2") (pinfunction "G2_G2") (pintype "passive"))
      (node (ref "U$1") (pin "10") (pinfunction "~{PRI_ON}_10") (pintype "bidirectional"))
    )
    (net (code "66") (name "VB_SEC_ON") (class "Default")
      (node (ref "Q1") (pin "G1") (pinfunction "G1_G1") (pintype "passive"))
      (node (ref "Q1") (pin "G2") (pinfunction "G2_G2") (pintype "passive"))
      (node (ref "U$1") (pin "9") (pinfunction "~{SEC_ON}_9") (pintype "bidirectional"))
    )
    (net (code "67") (name "VDD") (class "Default")
      (node (ref "C15") (pin "1") (pinfunction "1_1") (pintype "passive"))
      (node (ref "C16") (pin "1") (pinfunction "1_1") (pintype "passive"))
      (node (ref "C17") (pin "1") (pinfunction "1_1") (pintype "passive"))
      (node (ref "C2") (pin "1") (pinfunction "1_1") (pintype "passive"))
      (node (ref "J5") (pin "1") (pinfunction "VCC_1") (pintype "bidirectional"))
      (node (ref "R1") (pin "2") (pinfunction "2_2") (pintype "passive"))
      (node (ref "R8") (pin "2") (pinfunction "2_2") (pintype "passive"))
      (node (ref "U$3") (pin "16") (pinfunction "VCC_16") (pintype "bidirectional"))
      (node (ref "U1") (pin "5") (pinfunction "OUT_5") (pintype "passive"))
      (node (ref "U2") (pin "13") (pinfunction "VDD_13") (pintype "bidirectional"))
      (node (ref "U2") (pin "36") (pinfunction "VDD_36") (pintype "bidirectional"))
      (node (ref "U2") (pin "48") (pinfunction "VDD_48") (pintype "bidirectional"))
    )
    (net (code "68") (name "VIN") (class "Default")
      (node (ref "C1") (pin "1") (pinfunction "1_1") (pintype "passive"))
      (node (ref "JP1") (pin "2") (pinfunction "2_2") (pintype "passive"))
      (node (ref "JP2") (pin "1") (pinfunction "1_1") (pintype "passive"))
      (node (ref "U1") (pin "1") (pinfunction "IN_1") (pintype "input"))
      (node (ref "U1") (pin "3") (pinfunction "EN_3") (pintype "input"))
    )
    (net (code "69") (name "VIN_SOLAR") (class "Default")
      (node (ref "C7") (pin "2") (pinfunction "2_2") (pintype "passive"))
      (node (ref "C8") (pin "2") (pinfunction "2_2") (pintype "passive"))
      (node (ref "J2") (pin "1") (pinfunction "1_1") (pintype "passive"))
      (node (ref "U$1") (pin "2") (pinfunction "VIN_DC_2") (pintype "bidirectional"))
      (node (ref "U$2") (pin "P$1") (pinfunction "1_P$1") (pintype "passive"))
    )
    (net (code "70") (name "VRDIV") (class "Default")
      (node (ref "R3") (pin "2") (pinfunction "2_2") (pintype "passive"))
      (node (ref "R7") (pin "2") (pinfunction "2_2") (pintype "passive"))
      (node (ref "U$1") (pin "8") (pinfunction "VRDV_8") (pintype "bidirectional"))
    )
    (net (code "71") (name "VSTOR") (class "Default")
      (node (ref "C20") (pin "2") (pinfunction "2_2") (pintype "passive"))
      (node (ref "C21") (pin "2") (pinfunction "2_2") (pintype "passive"))
      (node (ref "JP2") (pin "2") (pinfunction "2_2") (pintype "passive"))
      (node (ref "Q1") (pin "D2") (pinfunction "D2_D2") (pintype "passive"))
      (node (ref "U$1") (pin "19") (pinfunction "VSTOR_19") (pintype "bidirectional"))
      (node (ref "U$1") (pin "3") (pinfunction "VOC_SAMP_3") (pintype "bidirectional"))
    )
    (net (code "72") (name "unconnected-(J1-CTS-Pad5)") (class "Default")
      (node (ref "J1") (pin "5") (pinfunction "CTS_5") (pintype "passive"))
    )
    (net (code "73") (name "unconnected-(J1-DTR-Pad1)") (class "Default")
      (node (ref "J1") (pin "1") (pinfunction "DTR_1") (pintype "passive"))
    )
    (net (code "74") (name "unconnected-(J5-KEY-Pad7)") (class "Default")
      (node (ref "J5") (pin "7") (pinfunction "KEY_7") (pintype "bidirectional"))
    )
    (net (code "75") (name "unconnected-(J5-NC{slash}TDI-Pad8)") (class "Default")
      (node (ref "J5") (pin "8") (pinfunction "NC/TDI_8") (pintype "bidirectional"))
    )
    (net (code "76") (name "unconnected-(Q1-PadS1)") (class "Default")
      (node (ref "Q1") (pin "S1") (pinfunction "S1_S1") (pintype "passive"))
    )
    (net (code "77") (name "unconnected-(Q1-PadS2)") (class "Default")
      (node (ref "Q1") (pin "S2") (pinfunction "S2_S2") (pintype "passive"))
    )
    (net (code "78") (name "unconnected-(Q2-PadS1)") (class "Default")
      (node (ref "Q2") (pin "S1") (pinfunction "S1_S1") (pintype "passive"))
    )
    (net (code "79") (name "unconnected-(Q2-PadS2)") (class "Default")
      (node (ref "Q2") (pin "S2") (pinfunction "S2_S2") (pintype "passive"))
    )
    (net (code "80") (name "unconnected-(U1-NC-Pad4)") (class "Default")
      (node (ref "U1") (pin "4") (pinfunction "NC_4") (pintype "input"))
    )
    (net (code "81") (name "unconnected-(U2-DCC-Pad47)") (class "Default")
      (node (ref "U2") (pin "47") (pinfunction "DCC_47") (pintype "bidirectional"))
    )
    (net (code "82") (name "unconnected-(U2-NC-Pad44)") (class "Default")
      (node (ref "U2") (pin "44") (pinfunction "NC_44") (pintype "bidirectional"))
    )
    (net (code "83") (name "~{RESET}") (class "Default")
      (node (ref "J5") (pin "10") (pinfunction "~{RESET}_10") (pintype "bidirectional"))
      (node (ref "SW1") (pin "1") (pinfunction "1_1") (pintype "passive"))
      (node (ref "SW1") (pin "2") (pinfunction "2_2") (pintype "passive"))
      (node (ref "U2") (pin "24") (pinfunction "P0.21/RESET_24") (pintype "bidirectional"))
    )
  )
)
